# GateDriver.net
KiCad netlist of a schematic drawn in Altium Designer
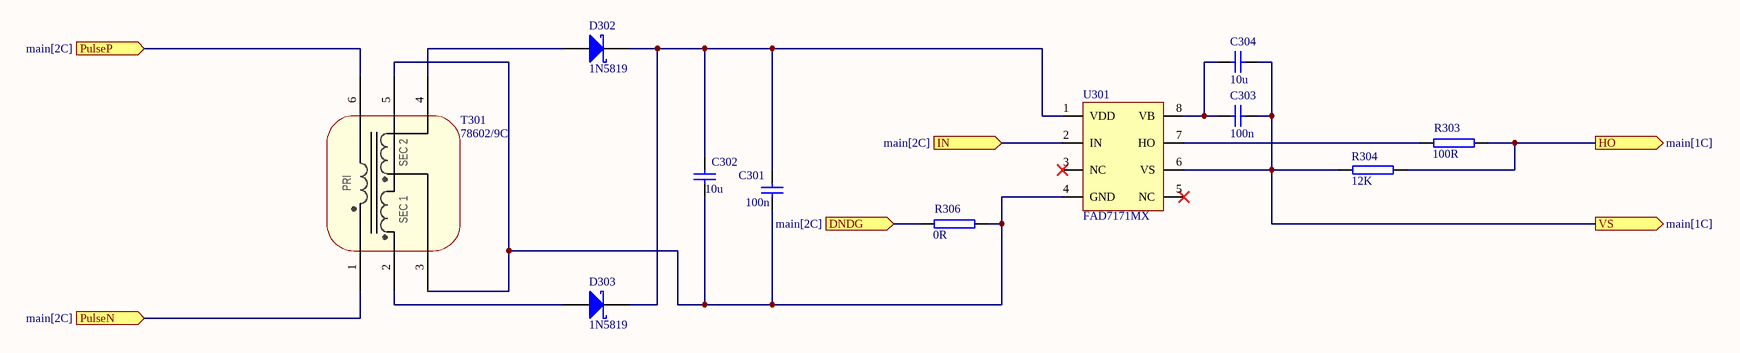
[diagram p0: GateDriver.SchDoc]

(export (version "E")
  (design (tool "Eeschema 10.0.6"))
  (components
    (comp (ref "C301")
      (value "100n")
      (footprint "CAP_1206")
      (description "Non Polarized Capacitor, SMD, 1206")
      (libsource (lib "Resistors and Capacitors") (part "CAPN 1206"))
    )
    (comp (ref "C302")
      (value "10u")
      (footprint "CAP_1206")
      (description "Non Polarized Capacitor, SMD, 1206")
      (libsource (lib "Resistors and Capacitors") (part "CAPN 1206"))
    )
    (comp (ref "C303")
      (value "100n")
      (footprint "RAD-0.2_AUT")
      (description "Non Polarized Capacitor, Multilayer Ceramic Dipped Radial, Pitch 200mil")
      (libsource (lib "Resistors and Capacitors") (part "CAPN RAD0.2"))
    )
    (comp (ref "C304")
      (value "10u")
      (footprint "CAP_1206")
      (description "Non Polarized Capacitor, SMD, 1206")
      (libsource (lib "Resistors and Capacitors") (part "CAPN 1206"))
    )
    (comp (ref "D302")
      (value "1N5819")
      (footprint "DIODE0.4_AUT")
      (description "Schottky Diode, 1A,40v")
      (libsource (lib "Diodes") (part "1N5819"))
    )
    (comp (ref "D303")
      (value "1N5819")
      (footprint "DIODE0.4_AUT")
      (description "Schottky Diode, 1A,40v")
      (libsource (lib "Diodes") (part "1N5819"))
    )
    (comp (ref "R303")
      (value "100R")
      (footprint "RES_1206")
      (description "Resistor, SMD, 1206")
      (libsource (lib "Resistors and Capacitors") (part "Resistor 1206"))
    )
    (comp (ref "R304")
      (value "12K")
      (footprint "RES_1206")
      (description "Resistor, SMD, 1206")
      (libsource (lib "Resistors and Capacitors") (part "Resistor 1206"))
    )
    (comp (ref "R306")
      (value "0R")
      (footprint "RES_1206")
      (description "Resistor, SMD, 1206")
      (libsource (lib "Resistors and Capacitors") (part "Resistor 1206"))
    )
    (comp (ref "T301")
      (value "78602/9C")
      (footprint "DIP6W_AUT")
      (description "Pulse transformer 1:1:1")
      (libsource (lib "Projects_2025") (part "78602/9C"))
    )
    (comp (ref "U301")
      (value "FAD7171MX")
      (footprint "SOIC8-M")
      (libsource (lib "Schlib") (part "FAD7171MX"))
    )
  )
  (nets
    (net (code "1") (name "/DNDG") (class "Default")
      (node (ref "R306") (pin "2") (pinfunction "2_2") (pintype "passive"))
    )
    (net (code "2") (name "/HO") (class "Default")
      (node (ref "R303") (pin "2") (pinfunction "2_2") (pintype "passive"))
      (node (ref "R304") (pin "1") (pinfunction "1_1") (pintype "passive"))
    )
    (net (code "3") (name "/IN") (class "Default")
      (node (ref "U301") (pin "2") (pinfunction "IN_2") (pintype "passive"))
    )
    (net (code "4") (name "/PulseN") (class "Default")
      (node (ref "T301") (pin "1") (pinfunction "Pri_1_1") (pintype "power_in"))
    )
    (net (code "5") (name "/PulseP") (class "Default")
      (node (ref "T301") (pin "6") (pinfunction "Pri2_6") (pintype "power_in"))
    )
    (net (code "6") (name "/VS") (class "Default")
      (node (ref "C303") (pin "2") (pinfunction "2_2") (pintype "passive"))
      (node (ref "C304") (pin "1") (pinfunction "1_1") (pintype "passive"))
      (node (ref "R304") (pin "2") (pinfunction "2_2") (pintype "passive"))
      (node (ref "U301") (pin "6") (pinfunction "VS_6") (pintype "passive"))
    )
    (net (code "7") (name "Net-(T301-Sec1_1)") (class "Default")
      (node (ref "D303") (pin "A") (pinfunction "A_A") (pintype "passive"))
      (node (ref "T301") (pin "2") (pinfunction "Sec1_1_2") (pintype "power_in"))
    )
    (net (code "8") (name "Net-(T301-Sec2_2)") (class "Default")
      (node (ref "D302") (pin "A") (pinfunction "A_A") (pintype "passive"))
      (node (ref "T301") (pin "4") (pinfunction "Sec2_2_4") (pintype "power_in"))
    )
    (net (code "9") (name "Net-(U301-GND)") (class "Default")
      (node (ref "C301") (pin "1") (pinfunction "1_1") (pintype "passive"))
      (node (ref "C302") (pin "1") (pinfunction "1_1") (pintype "passive"))
      (node (ref "R306") (pin "1") (pinfunction "1_1") (pintype "passive"))
      (node (ref "T301") (pin "3") (pinfunction "Sec1_2_3") (pintype "power_in"))
      (node (ref "T301") (pin "5") (pinfunction "Sec1_2_5") (pintype "power_in"))
      (node (ref "U301") (pin "4") (pinfunction "GND_4") (pintype "passive"))
    )
    (net (code "10") (name "Net-(U301-HO)") (class "Default")
      (node (ref "R303") (pin "1") (pinfunction "1_1") (pintype "passive"))
      (node (ref "U301") (pin "7") (pinfunction "HO_7") (pintype "passive"))
    )
    (net (code "11") (name "Net-(U301-VB)") (class "Default")
      (node (ref "C303") (pin "1") (pinfunction "1_1") (pintype "passive"))
      (node (ref "C304") (pin "2") (pinfunction "2_2") (pintype "passive"))
      (node (ref "U301") (pin "8") (pinfunction "VB_8") (pintype "passive"))
    )
    (net (code "12") (name "Net-(U301-VDD)") (class "Default")
      (node (ref "C301") (pin "2") (pinfunction "2_2") (pintype "passive"))
      (node (ref "C302") (pin "2") (pinfunction "2_2") (pintype "passive"))
      (node (ref "D302") (pin "K") (pinfunction "K_K") (pintype "passive"))
      (node (ref "D303") (pin "K") (pinfunction "K_K") (pintype "passive"))
      (node (ref "U301") (pin "1") (pinfunction "VDD_1") (pintype "passive"))
    )
    (net (code "13") (name "unconnected-(U301-NC-Pad3)") (class "Default")
      (node (ref "U301") (pin "3") (pinfunction "NC_3") (pintype "passive+no_connect"))
    )
    (net (code "14") (name "unconnected-(U301-NC-Pad5)") (class "Default")
      (node (ref "U301") (pin "5") (pinfunction "NC_5") (pintype "passive+no_connect"))
    )
  )
)
